# CC_LED_Driver.net
KiCad netlist of a schematic drawn in Altium Designer
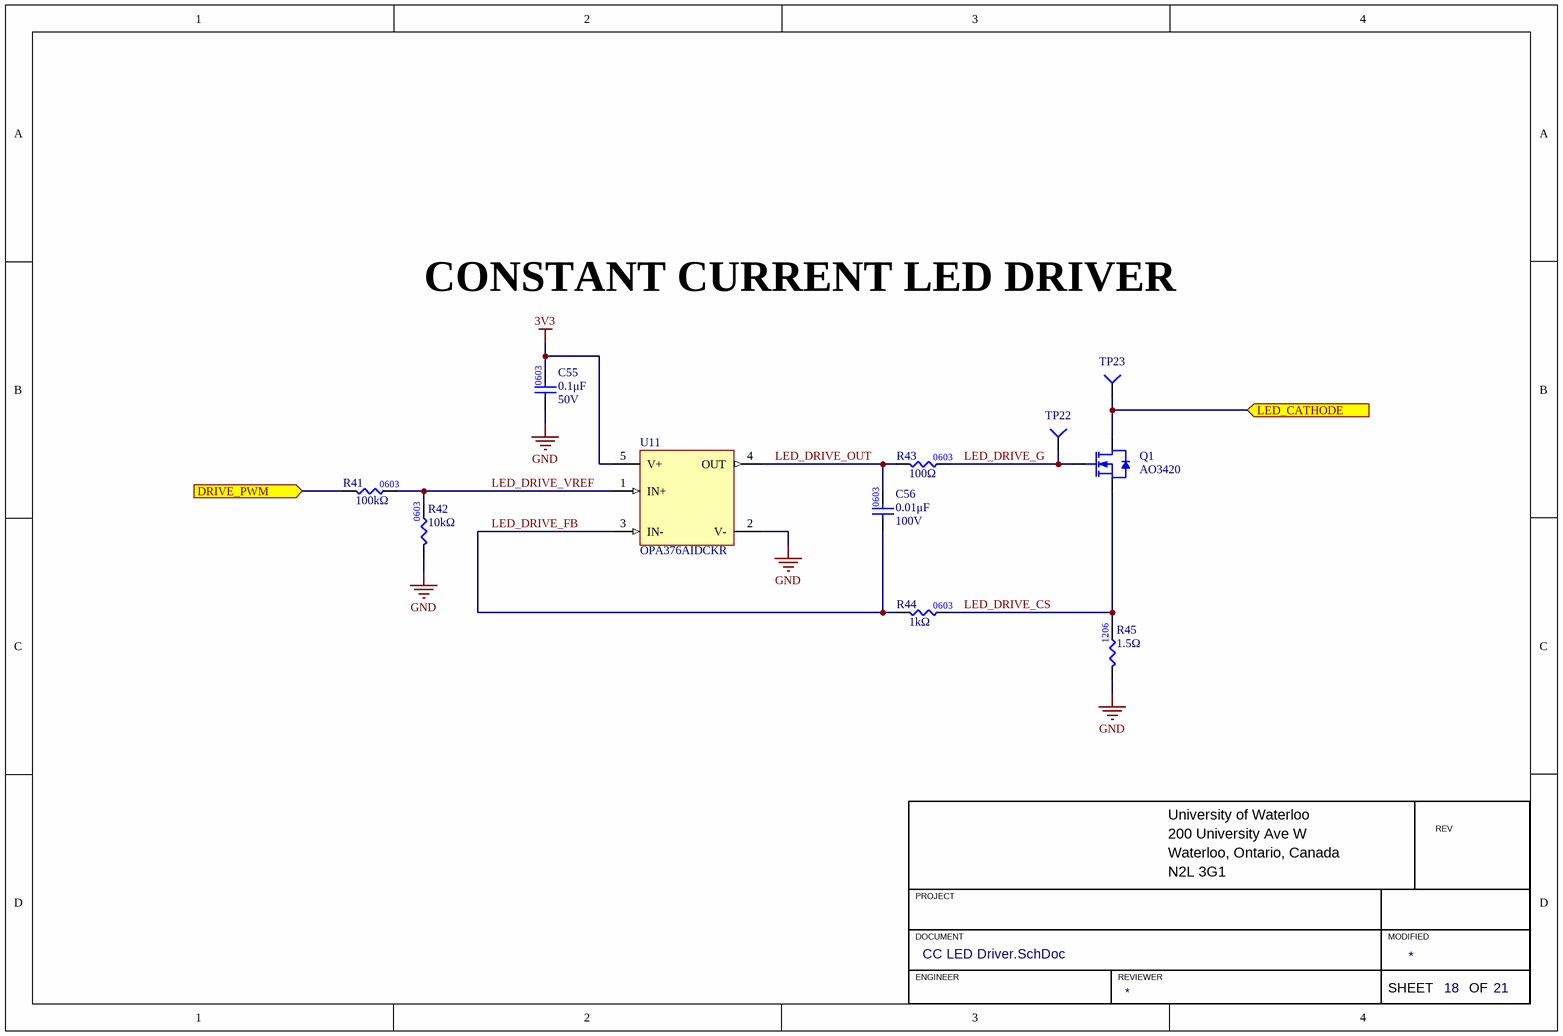
[diagram p0: CC LED Driver.SchDoc]

(export (version "E")
  (design (tool "Eeschema 10.0.6"))
  (components
    (comp (ref "C55")
      (value "0.1μF")
      (footprint "CAP0603")
      (description "CAP CER 0.1UF 50V X7R 0603")
      (fields (field (name "VOLTAGE RATING") "50V") (field (name "Comment") "CAP_0.1uF_50V_0603"))
      (libsource (lib "Personal_Schematic_Library_2022") (part "CAP_0.1uF_50V_0603"))
    )
    (comp (ref "C56")
      (value "0.01μF")
      (footprint "CAP0603")
      (description "CAP CER 0.01uF 100V X7R 0603")
      (fields (field (name "VOLTAGE RATING") "100V") (field (name "Comment") "CAP_0.01uF_100V_0603"))
      (libsource (lib "Personal_Schematic_Library_2022") (part "CAP_0.01uF_100V_0603"))
    )
    (comp (ref "Q1")
      (value "NMOS_20V_6A")
      (footprint "SOT23-3")
      (description "MOSFET N-CH 20V 6A SOT-23")
      (fields (field (name "MANUFACTURER PART NUMBER 1") "AO3420"))
      (libsource (lib "Personal_Schematic_Library_2022") (part "NMOS_20V_6A"))
    )
    (comp (ref "R41")
      (value "100kΩ")
      (footprint "RES0603")
      (description "RES 100K OHM 1% 1/10W 0603")
      (fields (field (name "Comment") "RES_100kΩ_0603_1%"))
      (libsource (lib "Personal_Schematic_Library_2022") (part "RES_100kΩ_0603_1%"))
    )
    (comp (ref "R42")
      (value "10kΩ")
      (footprint "RES0603")
      (description "RES 10K OHM 1% 1/8W 0603")
      (fields (field (name "Comment") "RES_10kΩ_0603_1%"))
      (libsource (lib "Personal_Schematic_Library_2022") (part "RES_10kΩ_0603_1%"))
    )
    (comp (ref "R43")
      (value "100Ω")
      (footprint "RES0603")
      (description "RES 100 OHM 1% 1/10W 0603")
      (fields (field (name "Comment") "RES_100Ω_0603_1%"))
      (libsource (lib "Personal_Schematic_Library_2022") (part "RES_100Ω_0603_1%"))
    )
    (comp (ref "R44")
      (value "1kΩ")
      (footprint "RES0603")
      (description "RES 1K OHM 1% 1/8W 0603")
      (fields (field (name "Comment") "RES_1kΩ_0603_1%"))
      (libsource (lib "Personal_Schematic_Library_2022") (part "RES_1kΩ_0603_1%"))
    )
    (comp (ref "R45")
      (value "1.5Ω")
      (footprint "RES1206")
      (description "RES 1.5 OHM 1% 1/4W 1206")
      (fields (field (name "POWER") "1/4W") (field (name "TOLERANCE") "1%"))
      (libsource (lib "Personal_Schematic_Library_2022") (part "RES_1.5Ω_1206_1%"))
    )
    (comp (ref "TP22")
      (value "TESTPOINT_1MM_CIRCLE")
      (footprint "TESTPOINT_CIRCLE_1MM")
      (description "TESTPOINT 1MM CIRCLE")
      (libsource (lib "Personal_Schematic_Library_2022") (part "TESTPOINT_1MM_CIRCLE"))
    )
    (comp (ref "TP23")
      (value "TESTPOINT_1MM_CIRCLE")
      (footprint "TESTPOINT_CIRCLE_1MM")
      (description "TESTPOINT 1MM CIRCLE")
      (libsource (lib "Personal_Schematic_Library_2022") (part "TESTPOINT_1MM_CIRCLE"))
    )
    (comp (ref "U11")
      (value "OPA376AIDCKR")
      (footprint "TI_SC-70-5")
      (description "IC OPAMP GP 1 CIRCUIT SC70-5")
      (fields (field (name "MANUFACTURER PART NUMBER 1") "OPA376AIDCKR"))
      (libsource (lib "Personal_Schematic_Library_2022") (part "OPA376AIDCKR"))
    )
  )
  (nets
    (net (code "1") (name "/DRIVE_PWM") (class "Default")
      (node (ref "R41") (pin "1") (pinfunction "1_1") (pintype "passive"))
    )
    (net (code "2") (name "/LED_CATHODE") (class "Default")
      (node (ref "Q1") (pin "3") (pinfunction "DRAIN_3") (pintype "passive"))
      (node (ref "TP23") (pin "1") (pinfunction "=value_1") (pintype "passive"))
    )
    (net (code "3") (name "/LED_DRIVE_CS") (class "Default")
      (node (ref "Q1") (pin "2") (pinfunction "SOURCE_2") (pintype "passive"))
      (node (ref "R44") (pin "2") (pinfunction "2_2") (pintype "passive"))
      (node (ref "R45") (pin "2") (pinfunction "2_2") (pintype "passive"))
    )
    (net (code "4") (name "/LED_DRIVE_FB") (class "Default")
      (node (ref "C56") (pin "1") (pinfunction "1_1") (pintype "passive"))
      (node (ref "R44") (pin "1") (pinfunction "1_1") (pintype "passive"))
      (node (ref "U11") (pin "3") (pinfunction "IN-_3") (pintype "input"))
    )
    (net (code "5") (name "/LED_DRIVE_G") (class "Default")
      (node (ref "Q1") (pin "1") (pinfunction "GATE_1") (pintype "passive"))
      (node (ref "R43") (pin "2") (pinfunction "2_2") (pintype "passive"))
      (node (ref "TP22") (pin "1") (pinfunction "=value_1") (pintype "passive"))
    )
    (net (code "6") (name "/LED_DRIVE_OUT") (class "Default")
      (node (ref "C56") (pin "2") (pinfunction "2_2") (pintype "passive"))
      (node (ref "R43") (pin "1") (pinfunction "1_1") (pintype "passive"))
      (node (ref "U11") (pin "4") (pinfunction "OUT_4") (pintype "output"))
    )
    (net (code "7") (name "/LED_DRIVE_VREF") (class "Default")
      (node (ref "R41") (pin "2") (pinfunction "2_2") (pintype "passive"))
      (node (ref "R42") (pin "2") (pinfunction "2_2") (pintype "passive"))
      (node (ref "U11") (pin "1") (pinfunction "IN+_1") (pintype "input"))
    )
    (net (code "8") (name "3V3") (class "Default")
      (node (ref "C55") (pin "2") (pinfunction "2_2") (pintype "passive"))
      (node (ref "U11") (pin "5") (pinfunction "V+_5") (pintype "power_in"))
    )
    (net (code "9") (name "GND") (class "Default")
      (node (ref "C55") (pin "1") (pinfunction "1_1") (pintype "passive"))
      (node (ref "R42") (pin "1") (pinfunction "1_1") (pintype "passive"))
      (node (ref "R45") (pin "1") (pinfunction "1_1") (pintype "passive"))
      (node (ref "U11") (pin "2") (pinfunction "V-_2") (pintype "power_in"))
    )
  )
)
